# juicy.net
KiCad netlist of a schematic drawn in EAGLE
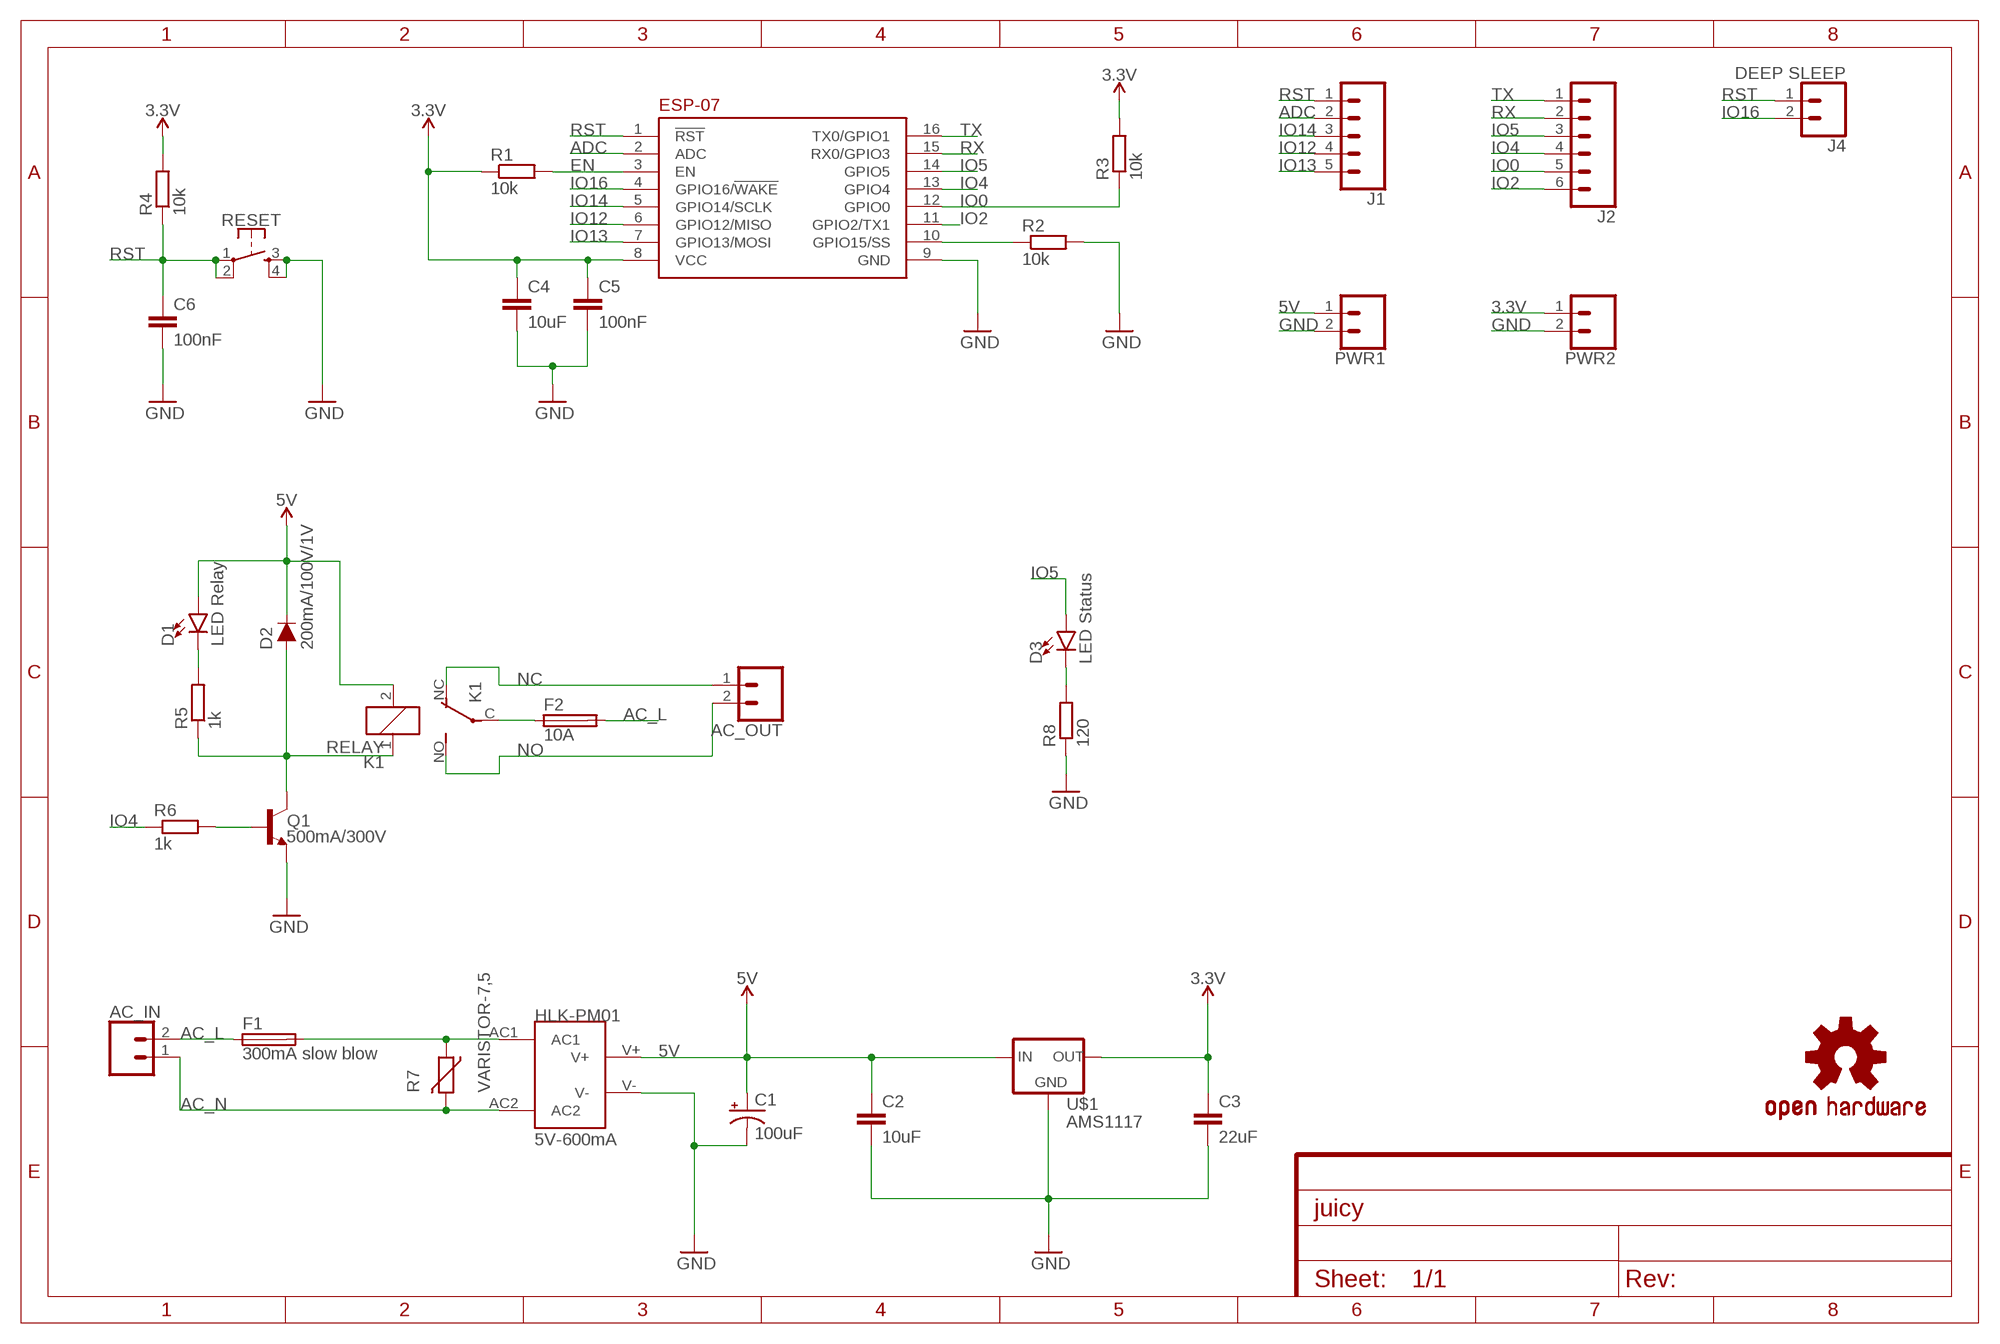
[diagram p0: schematic, sheet 1]

(export (version "E")
  (design (tool "Eeschema 10.0.6"))
  (components
    (comp (ref "AC_IN")
      (value "CONN_025MM")
      (footprint "eagle-import:SCREWTERMINAL-5MM-2")
      (libsource (lib "eagle-import") (part "CONN_025MM"))
    )
    (comp (ref "AC_OUT")
      (value "CONN_025MM")
      (footprint "eagle-import:SCREWTERMINAL-5MM-2")
      (libsource (lib "eagle-import") (part "CONN_025MM"))
    )
    (comp (ref "C1")
      (value "100uF")
      (footprint "eagle-import:PANASONIC_D")
      (libsource (lib "eagle-import") (part "100UF-POLAR-25V-20%(ELEC)"))
    )
    (comp (ref "C2")
      (value "10uF")
      (footprint "eagle-import:0805")
      (libsource (lib "eagle-import") (part "10UF-0805-10V-10%"))
    )
    (comp (ref "C3")
      (value "22uF")
      (footprint "eagle-import:0805")
      (libsource (lib "eagle-import") (part "22UF-0805-6.3V-20%"))
    )
    (comp (ref "C4")
      (value "10uF")
      (footprint "eagle-import:0805")
      (libsource (lib "eagle-import") (part "10UF-0805-10V-10%"))
    )
    (comp (ref "C5")
      (value "100nF")
      (footprint "eagle-import:0805")
      (libsource (lib "eagle-import") (part "10UF-0805-10V-10%"))
    )
    (comp (ref "C6")
      (value "100nF")
      (footprint "eagle-import:0805")
      (libsource (lib "eagle-import") (part "10UF-0805-10V-10%"))
    )
    (comp (ref "D1")
      (value "LED Relay")
      (footprint "eagle-import:LED_3MM")
      (libsource (lib "eagle-import") (part "LED3MM"))
    )
    (comp (ref "D2")
      (value "200mA/100V/1V")
      (footprint "eagle-import:DIODE-1N4148")
      (libsource (lib "eagle-import") (part "DIODE-1N4148"))
    )
    (comp (ref "D3")
      (value "LED Status")
      (footprint "eagle-import:LED_3MM")
      (libsource (lib "eagle-import") (part "LED3MM"))
    )
    (comp (ref "F1")
      (value "300mA slow blow")
      (footprint "eagle-import:SH22,5")
      (fields (field (name "MF") "SCHURTER") (field (name "MPN") "0031.8201"))
      (libsource (lib "eagle-import") (part "SH22,5"))
    )
    (comp (ref "F2")
      (value "10A")
      (footprint "eagle-import:SH22,5")
      (fields (field (name "MF") "SCHURTER") (field (name "MPN") "0031.8201"))
      (libsource (lib "eagle-import") (part "SH22,5"))
    )
    (comp (ref "J1")
      (value "CONN_05")
      (footprint "eagle-import:1X05")
      (libsource (lib "eagle-import") (part "CONN_05"))
    )
    (comp (ref "J2")
      (value "CONN_06SILK_FEMALE_PTH")
      (footprint "eagle-import:1X06")
      (libsource (lib "eagle-import") (part "CONN_06SILK_FEMALE_PTH"))
    )
    (comp (ref "J4")
      (value "DEEP SLEEP")
      (footprint "eagle-import:1X02")
      (libsource (lib "eagle-import") (part "CONN_02"))
    )
    (comp (ref "K1")
      (value "RELAY")
      (footprint "eagle-import:JS-M")
      (fields (field (name "MF") "FARNELL") (field (name "MPN") "JSM1-12V-5"))
      (libsource (lib "eagle-import") (part "JS-M1-12V-5"))
    )
    (comp (ref "LOGO1")
      (value "OSHW-LOGOM")
      (footprint "eagle-import:OSHW-LOGO-M")
      (libsource (lib "eagle-import") (part "OSHW-LOGOM"))
    )
    (comp (ref "PWR1")
      (value "CONN_02")
      (footprint "eagle-import:1X02")
      (libsource (lib "eagle-import") (part "CONN_02"))
    )
    (comp (ref "PWR2")
      (value "CONN_02")
      (footprint "eagle-import:1X02")
      (libsource (lib "eagle-import") (part "CONN_02"))
    )
    (comp (ref "Q1")
      (value "500mA/300V")
      (footprint "eagle-import:SOT23-3")
      (libsource (lib "eagle-import") (part "TRANS_NPN-MMBTA42"))
    )
    (comp (ref "R1")
      (value "10k")
      (footprint "eagle-import:R0805")
      (libsource (lib "eagle-import") (part "R-EU_R0805"))
    )
    (comp (ref "R2")
      (value "10k")
      (footprint "eagle-import:R0805")
      (libsource (lib "eagle-import") (part "R-EU_R0805"))
    )
    (comp (ref "R3")
      (value "10k")
      (footprint "eagle-import:R0805")
      (libsource (lib "eagle-import") (part "R-EU_R0805"))
    )
    (comp (ref "R4")
      (value "10k")
      (footprint "eagle-import:R0805")
      (libsource (lib "eagle-import") (part "R-EU_R0805"))
    )
    (comp (ref "R5")
      (value "1k")
      (footprint "eagle-import:R0805")
      (libsource (lib "eagle-import") (part "R-EU_R0805"))
    )
    (comp (ref "R6")
      (value "1k")
      (footprint "eagle-import:R0805")
      (libsource (lib "eagle-import") (part "R-EU_R0805"))
    )
    (comp (ref "R7")
      (value "VARISTOR-7,5")
      (footprint "eagle-import:R-7,5")
      (libsource (lib "eagle-import") (part "VARISTOR-7,5"))
    )
    (comp (ref "R8")
      (value "120")
      (footprint "eagle-import:R0805")
      (libsource (lib "eagle-import") (part "R-EU_R0805"))
    )
    (comp (ref "RESET")
      (value "MOMENTARY-SWITCH-SPST-2-SMD-5.2MM")
      (footprint "eagle-import:TACTILE_SWITCH_SMD_5.2MM")
      (libsource (lib "eagle-import") (part "MOMENTARY-SWITCH-SPST-2-SMD-5.2MM"))
    )
    (comp (ref "U$1")
      (value "AMS1117")
      (footprint "eagle-import:SOT223")
      (libsource (lib "eagle-import") (part "AMS1117"))
    )
    (comp (ref "U$2")
      (value "ESP8266")
      (footprint "eagle-import:ESP8266")
      (libsource (lib "eagle-import") (part "ESP8266"))
    )
    (comp (ref "U$3")
      (value "HILINK")
      (footprint "eagle-import:HLK-PM01")
      (libsource (lib "eagle-import") (part "HILINK"))
    )
  )
  (nets
    (net (code "1") (name "/AC_L") (class "Default")
      (node (ref "AC_IN") (pin "2") (pinfunction "2_2") (pintype "passive"))
      (node (ref "F1") (pin "1") (pinfunction "1_1") (pintype "passive"))
      (node (ref "F2") (pin "2") (pinfunction "2_2") (pintype "passive"))
    )
    (net (code "2") (name "/AC_N") (class "Default")
      (node (ref "AC_IN") (pin "1") (pinfunction "1_1") (pintype "passive"))
      (node (ref "R7") (pin "2") (pinfunction "2_2") (pintype "passive"))
      (node (ref "U$3") (pin "AC2") (pinfunction "AC2_AC2") (pintype "bidirectional"))
    )
    (net (code "3") (name "/ADC") (class "Default")
      (node (ref "J1") (pin "2") (pinfunction "2_2") (pintype "passive"))
      (node (ref "U$2") (pin "2") (pinfunction "ADC_2") (pintype "bidirectional"))
    )
    (net (code "4") (name "/EN") (class "Default")
      (node (ref "R1") (pin "2") (pinfunction "2_2") (pintype "passive"))
      (node (ref "U$2") (pin "3") (pinfunction "EN_3") (pintype "bidirectional"))
    )
    (net (code "5") (name "/IO0") (class "Default")
      (node (ref "J2") (pin "5") (pinfunction "5_5") (pintype "passive"))
      (node (ref "R3") (pin "1") (pinfunction "1_1") (pintype "passive"))
      (node (ref "U$2") (pin "12") (pinfunction "GPIO0_12") (pintype "bidirectional"))
    )
    (net (code "6") (name "/IO2") (class "Default")
      (node (ref "J2") (pin "6") (pinfunction "6_6") (pintype "passive"))
      (node (ref "U$2") (pin "11") (pinfunction "GPIO2/TX1_11") (pintype "bidirectional"))
    )
    (net (code "7") (name "/IO4") (class "Default")
      (node (ref "J2") (pin "4") (pinfunction "4_4") (pintype "passive"))
      (node (ref "R6") (pin "1") (pinfunction "1_1") (pintype "passive"))
      (node (ref "U$2") (pin "13") (pinfunction "GPIO4_13") (pintype "bidirectional"))
    )
    (net (code "8") (name "/IO5") (class "Default")
      (node (ref "D3") (pin "A") (pinfunction "A_A") (pintype "passive"))
      (node (ref "J2") (pin "3") (pinfunction "3_3") (pintype "passive"))
      (node (ref "U$2") (pin "14") (pinfunction "GPIO5_14") (pintype "bidirectional"))
    )
    (net (code "9") (name "/IO12") (class "Default")
      (node (ref "J1") (pin "4") (pinfunction "4_4") (pintype "passive"))
      (node (ref "U$2") (pin "6") (pinfunction "GPIO12/MISO_6") (pintype "bidirectional"))
    )
    (net (code "10") (name "/IO13") (class "Default")
      (node (ref "J1") (pin "5") (pinfunction "5_5") (pintype "passive"))
      (node (ref "U$2") (pin "7") (pinfunction "GPIO13/MOSI_7") (pintype "bidirectional"))
    )
    (net (code "11") (name "/IO14") (class "Default")
      (node (ref "J1") (pin "3") (pinfunction "3_3") (pintype "passive"))
      (node (ref "U$2") (pin "5") (pinfunction "GPIO14/SCLK_5") (pintype "bidirectional"))
    )
    (net (code "12") (name "/IO16") (class "Default")
      (node (ref "J4") (pin "2") (pinfunction "2_2") (pintype "passive"))
      (node (ref "U$2") (pin "4") (pinfunction "GPIO16/~{WAKE}_4") (pintype "bidirectional"))
    )
    (net (code "13") (name "/NC") (class "Default")
      (node (ref "AC_OUT") (pin "1") (pinfunction "1_1") (pintype "passive"))
      (node (ref "K1") (pin "NC") (pinfunction "O_NC") (pintype "passive"))
    )
    (net (code "14") (name "/NO") (class "Default")
      (node (ref "AC_OUT") (pin "2") (pinfunction "2_2") (pintype "passive"))
      (node (ref "K1") (pin "NO") (pinfunction "S_NO") (pintype "passive"))
    )
    (net (code "15") (name "/RST") (class "Default")
      (node (ref "C6") (pin "1") (pinfunction "1_1") (pintype "passive"))
      (node (ref "J1") (pin "1") (pinfunction "1_1") (pintype "passive"))
      (node (ref "J4") (pin "1") (pinfunction "1_1") (pintype "passive"))
      (node (ref "R4") (pin "1") (pinfunction "1_1") (pintype "passive"))
      (node (ref "RESET") (pin "1") (pinfunction "1_1") (pintype "passive"))
      (node (ref "RESET") (pin "2") (pinfunction "2_2") (pintype "passive"))
      (node (ref "U$2") (pin "1") (pinfunction "~{RST}_1") (pintype "bidirectional"))
    )
    (net (code "16") (name "/RX") (class "Default")
      (node (ref "J2") (pin "2") (pinfunction "2_2") (pintype "passive"))
      (node (ref "U$2") (pin "15") (pinfunction "RX0/GPIO3_15") (pintype "bidirectional"))
    )
    (net (code "17") (name "/TX") (class "Default")
      (node (ref "J2") (pin "1") (pinfunction "1_1") (pintype "passive"))
      (node (ref "U$2") (pin "16") (pinfunction "TX0/GPIO1_16") (pintype "bidirectional"))
    )
    (net (code "18") (name "3.3V") (class "Default")
      (node (ref "C3") (pin "1") (pinfunction "1_1") (pintype "passive"))
      (node (ref "C4") (pin "1") (pinfunction "1_1") (pintype "passive"))
      (node (ref "C5") (pin "1") (pinfunction "1_1") (pintype "passive"))
      (node (ref "PWR2") (pin "1") (pinfunction "1_1") (pintype "passive"))
      (node (ref "R1") (pin "1") (pinfunction "1_1") (pintype "passive"))
      (node (ref "R3") (pin "2") (pinfunction "2_2") (pintype "passive"))
      (node (ref "R4") (pin "2") (pinfunction "2_2") (pintype "passive"))
      (node (ref "U$1") (pin "2") (pinfunction "OUT_2") (pintype "passive"))
      (node (ref "U$1") (pin "4") (pinfunction "OUT_4") (pintype "passive"))
      (node (ref "U$2") (pin "8") (pinfunction "VCC_8") (pintype "power_in"))
    )
    (net (code "19") (name "5V") (class "Default")
      (node (ref "C1") (pin "+") (pinfunction "+_+") (pintype "passive"))
      (node (ref "C2") (pin "1") (pinfunction "1_1") (pintype "passive"))
      (node (ref "D1") (pin "A") (pinfunction "A_A") (pintype "passive"))
      (node (ref "D2") (pin "C") (pinfunction "C_C") (pintype "passive"))
      (node (ref "K1") (pin "2") (pinfunction "2_2") (pintype "passive"))
      (node (ref "PWR1") (pin "1") (pinfunction "1_1") (pintype "passive"))
      (node (ref "U$1") (pin "3") (pinfunction "IN_3") (pintype "input"))
      (node (ref "U$3") (pin "V+") (pinfunction "V+_V+") (pintype "bidirectional"))
    )
    (net (code "20") (name "GND") (class "Default")
      (node (ref "C1") (pin "-") (pinfunction "-_-") (pintype "passive"))
      (node (ref "C2") (pin "2") (pinfunction "2_2") (pintype "passive"))
      (node (ref "C3") (pin "2") (pinfunction "2_2") (pintype "passive"))
      (node (ref "C4") (pin "2") (pinfunction "2_2") (pintype "passive"))
      (node (ref "C5") (pin "2") (pinfunction "2_2") (pintype "passive"))
      (node (ref "C6") (pin "2") (pinfunction "2_2") (pintype "passive"))
      (node (ref "PWR1") (pin "2") (pinfunction "2_2") (pintype "passive"))
      (node (ref "PWR2") (pin "2") (pinfunction "2_2") (pintype "passive"))
      (node (ref "Q1") (pin "2") (pinfunction "E_2") (pintype "passive"))
      (node (ref "R2") (pin "2") (pinfunction "2_2") (pintype "passive"))
      (node (ref "R8") (pin "1") (pinfunction "1_1") (pintype "passive"))
      (node (ref "RESET") (pin "3") (pinfunction "3_3") (pintype "passive"))
      (node (ref "RESET") (pin "4") (pinfunction "4_4") (pintype "passive"))
      (node (ref "U$1") (pin "1") (pinfunction "GND_1") (pintype "input"))
      (node (ref "U$2") (pin "9") (pinfunction "GND_9") (pintype "power_in"))
      (node (ref "U$3") (pin "V-") (pinfunction "V-_V-") (pintype "bidirectional"))
    )
    (net (code "21") (name "Net-(D1-C)") (class "Default")
      (node (ref "D1") (pin "K") (pinfunction "C_K") (pintype "passive"))
      (node (ref "R5") (pin "2") (pinfunction "2_2") (pintype "passive"))
    )
    (net (code "22") (name "Net-(D3-C)") (class "Default")
      (node (ref "D3") (pin "K") (pinfunction "C_K") (pintype "passive"))
      (node (ref "R8") (pin "2") (pinfunction "2_2") (pintype "passive"))
    )
    (net (code "23") (name "Net-(F1-Pad2)") (class "Default")
      (node (ref "F1") (pin "2") (pinfunction "2_2") (pintype "passive"))
      (node (ref "R7") (pin "1") (pinfunction "1_1") (pintype "passive"))
      (node (ref "U$3") (pin "AC1") (pinfunction "AC1_AC1") (pintype "bidirectional"))
    )
    (net (code "24") (name "Net-(K1B-P)") (class "Default")
      (node (ref "F2") (pin "1") (pinfunction "1_1") (pintype "passive"))
      (node (ref "K1") (pin "C") (pinfunction "P_C") (pintype "passive"))
    )
    (net (code "25") (name "Net-(Q1-B)") (class "Default")
      (node (ref "Q1") (pin "1") (pinfunction "B_1") (pintype "passive"))
      (node (ref "R6") (pin "2") (pinfunction "2_2") (pintype "passive"))
    )
    (net (code "26") (name "Net-(Q1-C)") (class "Default")
      (node (ref "D2") (pin "A") (pinfunction "A_A") (pintype "passive"))
      (node (ref "K1") (pin "1") (pinfunction "1_1") (pintype "passive"))
      (node (ref "Q1") (pin "3") (pinfunction "C_3") (pintype "passive"))
      (node (ref "R5") (pin "1") (pinfunction "1_1") (pintype "passive"))
    )
    (net (code "27") (name "Net-(U$2-GPIO15{slash}SS)") (class "Default")
      (node (ref "R2") (pin "1") (pinfunction "1_1") (pintype "passive"))
      (node (ref "U$2") (pin "10") (pinfunction "GPIO15/SS_10") (pintype "bidirectional"))
    )
  )
)
